# I2C_Multiplexer.net
KiCad netlist of a schematic drawn in Altium Designer
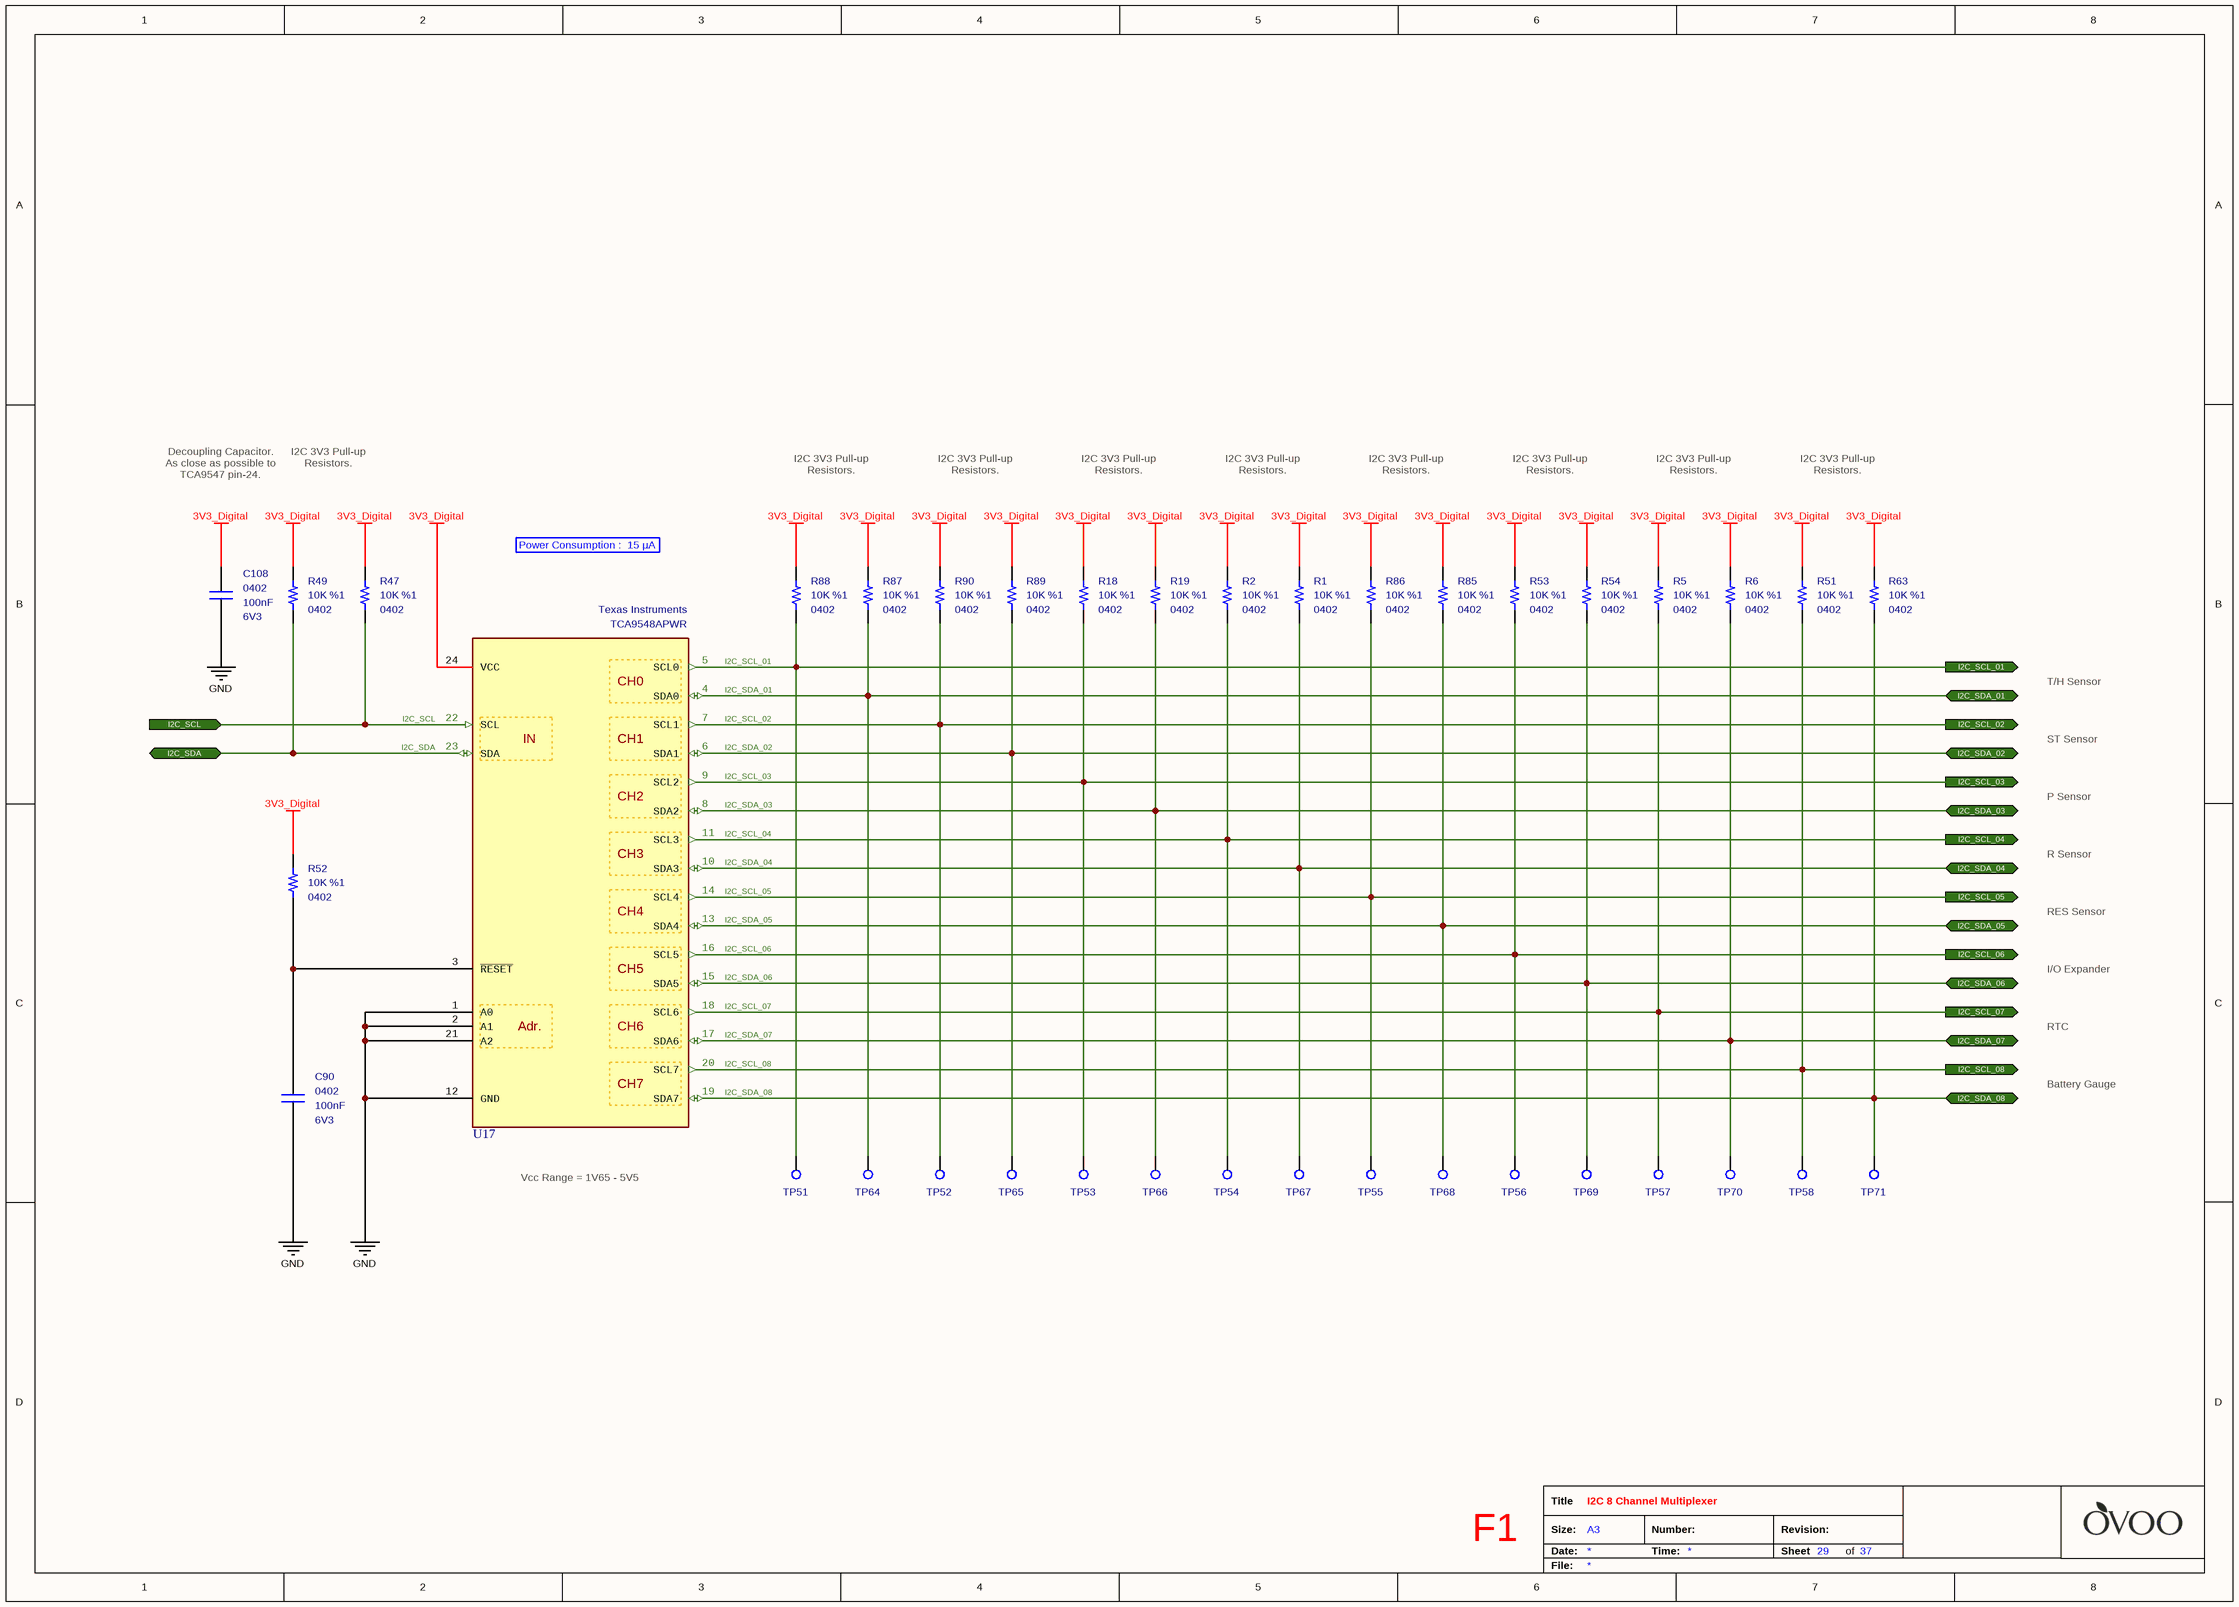
[diagram p0: I2C Multiplexer.SchDoc]

(export (version "E")
  (design (tool "Eeschema 10.0.6"))
  (components
    (comp (ref "C90")
      (value "100nF")
      (footprint "CAPACITOR_0402")
      (description "Capacitor - 100nF [0402-6V3] (Ceramic)")
      (fields
        (field (name "MANUFACTURER_PART_NUMBER") "04026D104KAT4A")
        (field (name "MOUSER_PART_NUMBER") "581-04026D104KAT4A")
        (field (name "CASE") "0402")
        (field (name "VOLTAGE") "6V3")
      )
      (libsource (lib "Ovoo_Schematic") (part "Capacitor - 100nF [0402-6V3]"))
    )
    (comp (ref "C108")
      (value "100nF")
      (footprint "CAPACITOR_0402")
      (description "Capacitor - 100nF [0402-6V3] (Ceramic)")
      (fields
        (field (name "MANUFACTURER_PART_NUMBER") "04026D104KAT4A")
        (field (name "MOUSER_PART_NUMBER") "581-04026D104KAT4A")
        (field (name "CASE") "0402")
        (field (name "VOLTAGE") "6V3")
      )
      (libsource (lib "Ovoo_Schematic") (part "Capacitor - 100nF [0402-6V3]"))
    )
    (comp (ref "R1")
      (value "10K")
      (footprint "RESISTOR_0402")
      (description "Thick Film Resistors - SMD 1/16 W 10 Kohms 1%")
      (fields
        (field (name "MANUFACTURER_PART_NUMBER") "CRCW040210K0FKED")
        (field (name "MOUSER_PART_NUMBER") "71-CRCW0402-10K-E3")
        (field (name "TOLERANCE") "%1")
        (field (name "CASE") "0402")
      )
      (libsource (lib "Ovoo_Schematic") (part "Resistor - 10K"))
    )
    (comp (ref "R2")
      (value "10K")
      (footprint "RESISTOR_0402")
      (description "Thick Film Resistors - SMD 1/16 W 10 Kohms 1%")
      (fields
        (field (name "MANUFACTURER_PART_NUMBER") "CRCW040210K0FKED")
        (field (name "MOUSER_PART_NUMBER") "71-CRCW0402-10K-E3")
        (field (name "TOLERANCE") "%1")
        (field (name "CASE") "0402")
      )
      (libsource (lib "Ovoo_Schematic") (part "Resistor - 10K"))
    )
    (comp (ref "R5")
      (value "10K")
      (footprint "RESISTOR_0402")
      (description "Thick Film Resistors - SMD 1/16 W 10 Kohms 1%")
      (fields
        (field (name "MANUFACTURER_PART_NUMBER") "CRCW040210K0FKED")
        (field (name "MOUSER_PART_NUMBER") "71-CRCW0402-10K-E3")
        (field (name "TOLERANCE") "%1")
        (field (name "CASE") "0402")
      )
      (libsource (lib "Ovoo_Schematic") (part "Resistor - 10K"))
    )
    (comp (ref "R6")
      (value "10K")
      (footprint "RESISTOR_0402")
      (description "Thick Film Resistors - SMD 1/16 W 10 Kohms 1%")
      (fields
        (field (name "MANUFACTURER_PART_NUMBER") "CRCW040210K0FKED")
        (field (name "MOUSER_PART_NUMBER") "71-CRCW0402-10K-E3")
        (field (name "TOLERANCE") "%1")
        (field (name "CASE") "0402")
      )
      (libsource (lib "Ovoo_Schematic") (part "Resistor - 10K"))
    )
    (comp (ref "R18")
      (value "10K")
      (footprint "RESISTOR_0402")
      (description "Thick Film Resistors - SMD 1/16 W 10 Kohms 1%")
      (fields
        (field (name "MANUFACTURER_PART_NUMBER") "CRCW040210K0FKED")
        (field (name "MOUSER_PART_NUMBER") "71-CRCW0402-10K-E3")
        (field (name "TOLERANCE") "%1")
        (field (name "CASE") "0402")
      )
      (libsource (lib "Ovoo_Schematic") (part "Resistor - 10K"))
    )
    (comp (ref "R19")
      (value "10K")
      (footprint "RESISTOR_0402")
      (description "Thick Film Resistors - SMD 1/16 W 10 Kohms 1%")
      (fields
        (field (name "MANUFACTURER_PART_NUMBER") "CRCW040210K0FKED")
        (field (name "MOUSER_PART_NUMBER") "71-CRCW0402-10K-E3")
        (field (name "TOLERANCE") "%1")
        (field (name "CASE") "0402")
      )
      (libsource (lib "Ovoo_Schematic") (part "Resistor - 10K"))
    )
    (comp (ref "R47")
      (value "10K")
      (footprint "RESISTOR_0402")
      (description "Thick Film Resistors - SMD 1/16 W 10 Kohms 1%")
      (fields
        (field (name "MANUFACTURER_PART_NUMBER") "CRCW040210K0FKED")
        (field (name "MOUSER_PART_NUMBER") "71-CRCW0402-10K-E3")
        (field (name "TOLERANCE") "%1")
        (field (name "CASE") "0402")
      )
      (libsource (lib "Ovoo_Schematic") (part "Resistor - 10K"))
    )
    (comp (ref "R49")
      (value "10K")
      (footprint "RESISTOR_0402")
      (description "Thick Film Resistors - SMD 1/16 W 10 Kohms 1%")
      (fields
        (field (name "MANUFACTURER_PART_NUMBER") "CRCW040210K0FKED")
        (field (name "MOUSER_PART_NUMBER") "71-CRCW0402-10K-E3")
        (field (name "TOLERANCE") "%1")
        (field (name "CASE") "0402")
      )
      (libsource (lib "Ovoo_Schematic") (part "Resistor - 10K"))
    )
    (comp (ref "R51")
      (value "10K")
      (footprint "RESISTOR_0402")
      (description "Thick Film Resistors - SMD 1/16 W 10 Kohms 1%")
      (fields
        (field (name "MANUFACTURER_PART_NUMBER") "CRCW040210K0FKED")
        (field (name "MOUSER_PART_NUMBER") "71-CRCW0402-10K-E3")
        (field (name "TOLERANCE") "%1")
        (field (name "CASE") "0402")
      )
      (libsource (lib "Ovoo_Schematic") (part "Resistor - 10K"))
    )
    (comp (ref "R52")
      (value "10K")
      (footprint "RESISTOR_0402")
      (description "Thick Film Resistors - SMD 1/16 W 10 Kohms 1%")
      (fields
        (field (name "MANUFACTURER_PART_NUMBER") "CRCW040210K0FKED")
        (field (name "MOUSER_PART_NUMBER") "71-CRCW0402-10K-E3")
        (field (name "TOLERANCE") "%1")
        (field (name "CASE") "0402")
      )
      (libsource (lib "Ovoo_Schematic") (part "Resistor - 10K"))
    )
    (comp (ref "R53")
      (value "10K")
      (footprint "RESISTOR_0402")
      (description "Thick Film Resistors - SMD 1/16 W 10 Kohms 1%")
      (fields
        (field (name "MANUFACTURER_PART_NUMBER") "CRCW040210K0FKED")
        (field (name "MOUSER_PART_NUMBER") "71-CRCW0402-10K-E3")
        (field (name "TOLERANCE") "%1")
        (field (name "CASE") "0402")
      )
      (libsource (lib "Ovoo_Schematic") (part "Resistor - 10K"))
    )
    (comp (ref "R54")
      (value "10K")
      (footprint "RESISTOR_0402")
      (description "Thick Film Resistors - SMD 1/16 W 10 Kohms 1%")
      (fields
        (field (name "MANUFACTURER_PART_NUMBER") "CRCW040210K0FKED")
        (field (name "MOUSER_PART_NUMBER") "71-CRCW0402-10K-E3")
        (field (name "TOLERANCE") "%1")
        (field (name "CASE") "0402")
      )
      (libsource (lib "Ovoo_Schematic") (part "Resistor - 10K"))
    )
    (comp (ref "R63")
      (value "10K")
      (footprint "RESISTOR_0402")
      (description "Thick Film Resistors - SMD 1/16 W 10 Kohms 1%")
      (fields
        (field (name "MANUFACTURER_PART_NUMBER") "CRCW040210K0FKED")
        (field (name "MOUSER_PART_NUMBER") "71-CRCW0402-10K-E3")
        (field (name "TOLERANCE") "%1")
        (field (name "CASE") "0402")
      )
      (libsource (lib "Ovoo_Schematic") (part "Resistor - 10K"))
    )
    (comp (ref "R85")
      (value "10K")
      (footprint "RESISTOR_0402")
      (description "Thick Film Resistors - SMD 1/16 W 10 Kohms 1%")
      (fields
        (field (name "MANUFACTURER_PART_NUMBER") "CRCW040210K0FKED")
        (field (name "MOUSER_PART_NUMBER") "71-CRCW0402-10K-E3")
        (field (name "TOLERANCE") "%1")
        (field (name "CASE") "0402")
      )
      (libsource (lib "Ovoo_Schematic") (part "Resistor - 10K"))
    )
    (comp (ref "R86")
      (value "10K")
      (footprint "RESISTOR_0402")
      (description "Thick Film Resistors - SMD 1/16 W 10 Kohms 1%")
      (fields
        (field (name "MANUFACTURER_PART_NUMBER") "CRCW040210K0FKED")
        (field (name "MOUSER_PART_NUMBER") "71-CRCW0402-10K-E3")
        (field (name "TOLERANCE") "%1")
        (field (name "CASE") "0402")
      )
      (libsource (lib "Ovoo_Schematic") (part "Resistor - 10K"))
    )
    (comp (ref "R87")
      (value "10K")
      (footprint "RESISTOR_0402")
      (description "Thick Film Resistors - SMD 1/16 W 10 Kohms 1%")
      (fields
        (field (name "MANUFACTURER_PART_NUMBER") "CRCW040210K0FKED")
        (field (name "MOUSER_PART_NUMBER") "71-CRCW0402-10K-E3")
        (field (name "TOLERANCE") "%1")
        (field (name "CASE") "0402")
      )
      (libsource (lib "Ovoo_Schematic") (part "Resistor - 10K"))
    )
    (comp (ref "R88")
      (value "10K")
      (footprint "RESISTOR_0402")
      (description "Thick Film Resistors - SMD 1/16 W 10 Kohms 1%")
      (fields
        (field (name "MANUFACTURER_PART_NUMBER") "CRCW040210K0FKED")
        (field (name "MOUSER_PART_NUMBER") "71-CRCW0402-10K-E3")
        (field (name "TOLERANCE") "%1")
        (field (name "CASE") "0402")
      )
      (libsource (lib "Ovoo_Schematic") (part "Resistor - 10K"))
    )
    (comp (ref "R89")
      (value "10K")
      (footprint "RESISTOR_0402")
      (description "Thick Film Resistors - SMD 1/16 W 10 Kohms 1%")
      (fields
        (field (name "MANUFACTURER_PART_NUMBER") "CRCW040210K0FKED")
        (field (name "MOUSER_PART_NUMBER") "71-CRCW0402-10K-E3")
        (field (name "TOLERANCE") "%1")
        (field (name "CASE") "0402")
      )
      (libsource (lib "Ovoo_Schematic") (part "Resistor - 10K"))
    )
    (comp (ref "R90")
      (value "10K")
      (footprint "RESISTOR_0402")
      (description "Thick Film Resistors - SMD 1/16 W 10 Kohms 1%")
      (fields
        (field (name "MANUFACTURER_PART_NUMBER") "CRCW040210K0FKED")
        (field (name "MOUSER_PART_NUMBER") "71-CRCW0402-10K-E3")
        (field (name "TOLERANCE") "%1")
        (field (name "CASE") "0402")
      )
      (libsource (lib "Ovoo_Schematic") (part "Resistor - 10K"))
    )
    (comp (ref "TP51")
      (value "PCB - Test Point")
      (footprint "Test_Pad - Hole")
      (description "Test Point")
      (libsource (lib "Ovoo_Schematic") (part "PCB - Test Point"))
    )
    (comp (ref "TP52")
      (value "PCB - Test Point")
      (footprint "Test_Pad - Hole")
      (description "Test Point")
      (libsource (lib "Ovoo_Schematic") (part "PCB - Test Point"))
    )
    (comp (ref "TP53")
      (value "PCB - Test Point")
      (footprint "Test_Pad - Hole")
      (description "Test Point")
      (libsource (lib "Ovoo_Schematic") (part "PCB - Test Point"))
    )
    (comp (ref "TP54")
      (value "PCB - Test Point")
      (footprint "Test_Pad - Hole")
      (description "Test Point")
      (libsource (lib "Ovoo_Schematic") (part "PCB - Test Point"))
    )
    (comp (ref "TP55")
      (value "PCB - Test Point")
      (footprint "Test_Pad - Hole")
      (description "Test Point")
      (libsource (lib "Ovoo_Schematic") (part "PCB - Test Point"))
    )
    (comp (ref "TP56")
      (value "PCB - Test Point")
      (footprint "Test_Pad - Hole")
      (description "Test Point")
      (libsource (lib "Ovoo_Schematic") (part "PCB - Test Point"))
    )
    (comp (ref "TP57")
      (value "PCB - Test Point")
      (footprint "Test_Pad - Hole")
      (description "Test Point")
      (libsource (lib "Ovoo_Schematic") (part "PCB - Test Point"))
    )
    (comp (ref "TP58")
      (value "PCB - Test Point")
      (footprint "Test_Pad - Hole")
      (description "Test Point")
      (libsource (lib "Ovoo_Schematic") (part "PCB - Test Point"))
    )
    (comp (ref "TP64")
      (value "PCB - Test Point")
      (footprint "Test_Pad - Hole")
      (description "Test Point")
      (libsource (lib "Ovoo_Schematic") (part "PCB - Test Point"))
    )
    (comp (ref "TP65")
      (value "PCB - Test Point")
      (footprint "Test_Pad - Hole")
      (description "Test Point")
      (libsource (lib "Ovoo_Schematic") (part "PCB - Test Point"))
    )
    (comp (ref "TP66")
      (value "PCB - Test Point")
      (footprint "Test_Pad - Hole")
      (description "Test Point")
      (libsource (lib "Ovoo_Schematic") (part "PCB - Test Point"))
    )
    (comp (ref "TP67")
      (value "PCB - Test Point")
      (footprint "Test_Pad - Hole")
      (description "Test Point")
      (libsource (lib "Ovoo_Schematic") (part "PCB - Test Point"))
    )
    (comp (ref "TP68")
      (value "PCB - Test Point")
      (footprint "Test_Pad - Hole")
      (description "Test Point")
      (libsource (lib "Ovoo_Schematic") (part "PCB - Test Point"))
    )
    (comp (ref "TP69")
      (value "PCB - Test Point")
      (footprint "Test_Pad - Hole")
      (description "Test Point")
      (libsource (lib "Ovoo_Schematic") (part "PCB - Test Point"))
    )
    (comp (ref "TP70")
      (value "PCB - Test Point")
      (footprint "Test_Pad - Hole")
      (description "Test Point")
      (libsource (lib "Ovoo_Schematic") (part "PCB - Test Point"))
    )
    (comp (ref "TP71")
      (value "PCB - Test Point")
      (footprint "Test_Pad - Hole")
      (description "Test Point")
      (libsource (lib "Ovoo_Schematic") (part "PCB - Test Point"))
    )
    (comp (ref "U17")
      (value "I2C Switch IC")
      (footprint "TSSOP-24")
      (description "Switch ICs - Various 8-Channel I2C Switch")
      (fields
        (field (name "MOUSER PART NUMBER") "595-TCA9548APWR")
        (field (name "MANUFACTURER_PART_NUMBER") "TCA9548APWR")
        (field (name "MANUFACTURER_NAME") "Texas Instruments")
      )
      (libsource (lib "Ovoo_Schematic") (part "IC - TCA9548APWR"))
    )
  )
  (nets
    (net (code "1") (name "/I2C_SCL") (class "Default")
      (node (ref "R47") (pin "1") (pinfunction "1_1") (pintype "passive"))
      (node (ref "U17") (pin "22") (pinfunction "SCL_22") (pintype "input"))
    )
    (net (code "2") (name "/I2C_SCL_01") (class "Default")
      (node (ref "R88") (pin "1") (pinfunction "1_1") (pintype "passive"))
      (node (ref "TP51") (pin "1") (pinfunction "1_1") (pintype "passive"))
      (node (ref "U17") (pin "5") (pinfunction "SCL0_5") (pintype "output"))
    )
    (net (code "3") (name "/I2C_SCL_02") (class "Default")
      (node (ref "R90") (pin "1") (pinfunction "1_1") (pintype "passive"))
      (node (ref "TP52") (pin "1") (pinfunction "1_1") (pintype "passive"))
      (node (ref "U17") (pin "7") (pinfunction "SCL1_7") (pintype "output"))
    )
    (net (code "4") (name "/I2C_SCL_03") (class "Default")
      (node (ref "R18") (pin "1") (pinfunction "1_1") (pintype "passive"))
      (node (ref "TP53") (pin "1") (pinfunction "1_1") (pintype "passive"))
      (node (ref "U17") (pin "9") (pinfunction "SCL2_9") (pintype "output"))
    )
    (net (code "5") (name "/I2C_SCL_04") (class "Default")
      (node (ref "R2") (pin "1") (pinfunction "1_1") (pintype "passive"))
      (node (ref "TP54") (pin "1") (pinfunction "1_1") (pintype "passive"))
      (node (ref "U17") (pin "11") (pinfunction "SCL3_11") (pintype "output"))
    )
    (net (code "6") (name "/I2C_SCL_05") (class "Default")
      (node (ref "R86") (pin "1") (pinfunction "1_1") (pintype "passive"))
      (node (ref "TP55") (pin "1") (pinfunction "1_1") (pintype "passive"))
      (node (ref "U17") (pin "14") (pinfunction "SCL4_14") (pintype "output"))
    )
    (net (code "7") (name "/I2C_SCL_06") (class "Default")
      (node (ref "R53") (pin "1") (pinfunction "1_1") (pintype "passive"))
      (node (ref "TP56") (pin "1") (pinfunction "1_1") (pintype "passive"))
      (node (ref "U17") (pin "16") (pinfunction "SCL5_16") (pintype "output"))
    )
    (net (code "8") (name "/I2C_SCL_07") (class "Default")
      (node (ref "R5") (pin "1") (pinfunction "1_1") (pintype "passive"))
      (node (ref "TP57") (pin "1") (pinfunction "1_1") (pintype "passive"))
      (node (ref "U17") (pin "18") (pinfunction "SCL6_18") (pintype "output"))
    )
    (net (code "9") (name "/I2C_SCL_08") (class "Default")
      (node (ref "R51") (pin "1") (pinfunction "1_1") (pintype "passive"))
      (node (ref "TP58") (pin "1") (pinfunction "1_1") (pintype "passive"))
      (node (ref "U17") (pin "20") (pinfunction "SCL7_20") (pintype "output"))
    )
    (net (code "10") (name "/I2C_SDA") (class "Default")
      (node (ref "R49") (pin "1") (pinfunction "1_1") (pintype "passive"))
      (node (ref "U17") (pin "23") (pinfunction "SDA_23") (pintype "bidirectional"))
    )
    (net (code "11") (name "/I2C_SDA_01") (class "Default")
      (node (ref "R87") (pin "1") (pinfunction "1_1") (pintype "passive"))
      (node (ref "TP64") (pin "1") (pinfunction "1_1") (pintype "passive"))
      (node (ref "U17") (pin "4") (pinfunction "SDA0_4") (pintype "bidirectional"))
    )
    (net (code "12") (name "/I2C_SDA_02") (class "Default")
      (node (ref "R89") (pin "1") (pinfunction "1_1") (pintype "passive"))
      (node (ref "TP65") (pin "1") (pinfunction "1_1") (pintype "passive"))
      (node (ref "U17") (pin "6") (pinfunction "SDA1_6") (pintype "bidirectional"))
    )
    (net (code "13") (name "/I2C_SDA_03") (class "Default")
      (node (ref "R19") (pin "1") (pinfunction "1_1") (pintype "passive"))
      (node (ref "TP66") (pin "1") (pinfunction "1_1") (pintype "passive"))
      (node (ref "U17") (pin "8") (pinfunction "SDA2_8") (pintype "bidirectional"))
    )
    (net (code "14") (name "/I2C_SDA_04") (class "Default")
      (node (ref "R1") (pin "1") (pinfunction "1_1") (pintype "passive"))
      (node (ref "TP67") (pin "1") (pinfunction "1_1") (pintype "passive"))
      (node (ref "U17") (pin "10") (pinfunction "SDA3_10") (pintype "bidirectional"))
    )
    (net (code "15") (name "/I2C_SDA_05") (class "Default")
      (node (ref "R85") (pin "1") (pinfunction "1_1") (pintype "passive"))
      (node (ref "TP68") (pin "1") (pinfunction "1_1") (pintype "passive"))
      (node (ref "U17") (pin "13") (pinfunction "SDA4_13") (pintype "bidirectional"))
    )
    (net (code "16") (name "/I2C_SDA_06") (class "Default")
      (node (ref "R54") (pin "1") (pinfunction "1_1") (pintype "passive"))
      (node (ref "TP69") (pin "1") (pinfunction "1_1") (pintype "passive"))
      (node (ref "U17") (pin "15") (pinfunction "SDA5_15") (pintype "bidirectional"))
    )
    (net (code "17") (name "/I2C_SDA_07") (class "Default")
      (node (ref "R6") (pin "1") (pinfunction "1_1") (pintype "passive"))
      (node (ref "TP70") (pin "1") (pinfunction "1_1") (pintype "passive"))
      (node (ref "U17") (pin "17") (pinfunction "SDA6_17") (pintype "bidirectional"))
    )
    (net (code "18") (name "/I2C_SDA_08") (class "Default")
      (node (ref "R63") (pin "1") (pinfunction "1_1") (pintype "passive"))
      (node (ref "TP71") (pin "1") (pinfunction "1_1") (pintype "passive"))
      (node (ref "U17") (pin "19") (pinfunction "SDA7_19") (pintype "bidirectional"))
    )
    (net (code "19") (name "3V3_Digital") (class "Default")
      (node (ref "C108") (pin "2") (pinfunction "2_2") (pintype "passive"))
      (node (ref "R1") (pin "2") (pinfunction "2_2") (pintype "passive"))
      (node (ref "R18") (pin "2") (pinfunction "2_2") (pintype "passive"))
      (node (ref "R19") (pin "2") (pinfunction "2_2") (pintype "passive"))
      (node (ref "R2") (pin "2") (pinfunction "2_2") (pintype "passive"))
      (node (ref "R47") (pin "2") (pinfunction "2_2") (pintype "passive"))
      (node (ref "R49") (pin "2") (pinfunction "2_2") (pintype "passive"))
      (node (ref "R5") (pin "2") (pinfunction "2_2") (pintype "passive"))
      (node (ref "R51") (pin "2") (pinfunction "2_2") (pintype "passive"))
      (node (ref "R52") (pin "2") (pinfunction "2_2") (pintype "passive"))
      (node (ref "R53") (pin "2") (pinfunction "2_2") (pintype "passive"))
      (node (ref "R54") (pin "2") (pinfunction "2_2") (pintype "passive"))
      (node (ref "R6") (pin "2") (pinfunction "2_2") (pintype "passive"))
      (node (ref "R63") (pin "2") (pinfunction "2_2") (pintype "passive"))
      (node (ref "R85") (pin "2") (pinfunction "2_2") (pintype "passive"))
      (node (ref "R86") (pin "2") (pinfunction "2_2") (pintype "passive"))
      (node (ref "R87") (pin "2") (pinfunction "2_2") (pintype "passive"))
      (node (ref "R88") (pin "2") (pinfunction "2_2") (pintype "passive"))
      (node (ref "R89") (pin "2") (pinfunction "2_2") (pintype "passive"))
      (node (ref "R90") (pin "2") (pinfunction "2_2") (pintype "passive"))
      (node (ref "U17") (pin "24") (pinfunction "VCC_24") (pintype "power_in"))
    )
    (net (code "20") (name "GND") (class "Default")
      (node (ref "C108") (pin "1") (pinfunction "1_1") (pintype "passive"))
      (node (ref "C90") (pin "1") (pinfunction "1_1") (pintype "passive"))
      (node (ref "U17") (pin "1") (pinfunction "A0_1") (pintype "passive"))
      (node (ref "U17") (pin "12") (pinfunction "GND_12") (pintype "power_in"))
      (node (ref "U17") (pin "2") (pinfunction "A1_2") (pintype "passive"))
      (node (ref "U17") (pin "21") (pinfunction "A2_21") (pintype "passive"))
    )
    (net (code "21") (name "Net-(U17-~{RESET})") (class "Default")
      (node (ref "C90") (pin "2") (pinfunction "2_2") (pintype "passive"))
      (node (ref "R52") (pin "1") (pinfunction "1_1") (pintype "passive"))
      (node (ref "U17") (pin "3") (pinfunction "~{RESET}_3") (pintype "power_in"))
    )
  )
)
